# MCU.net
KiCad netlist of a schematic drawn in Altium Designer
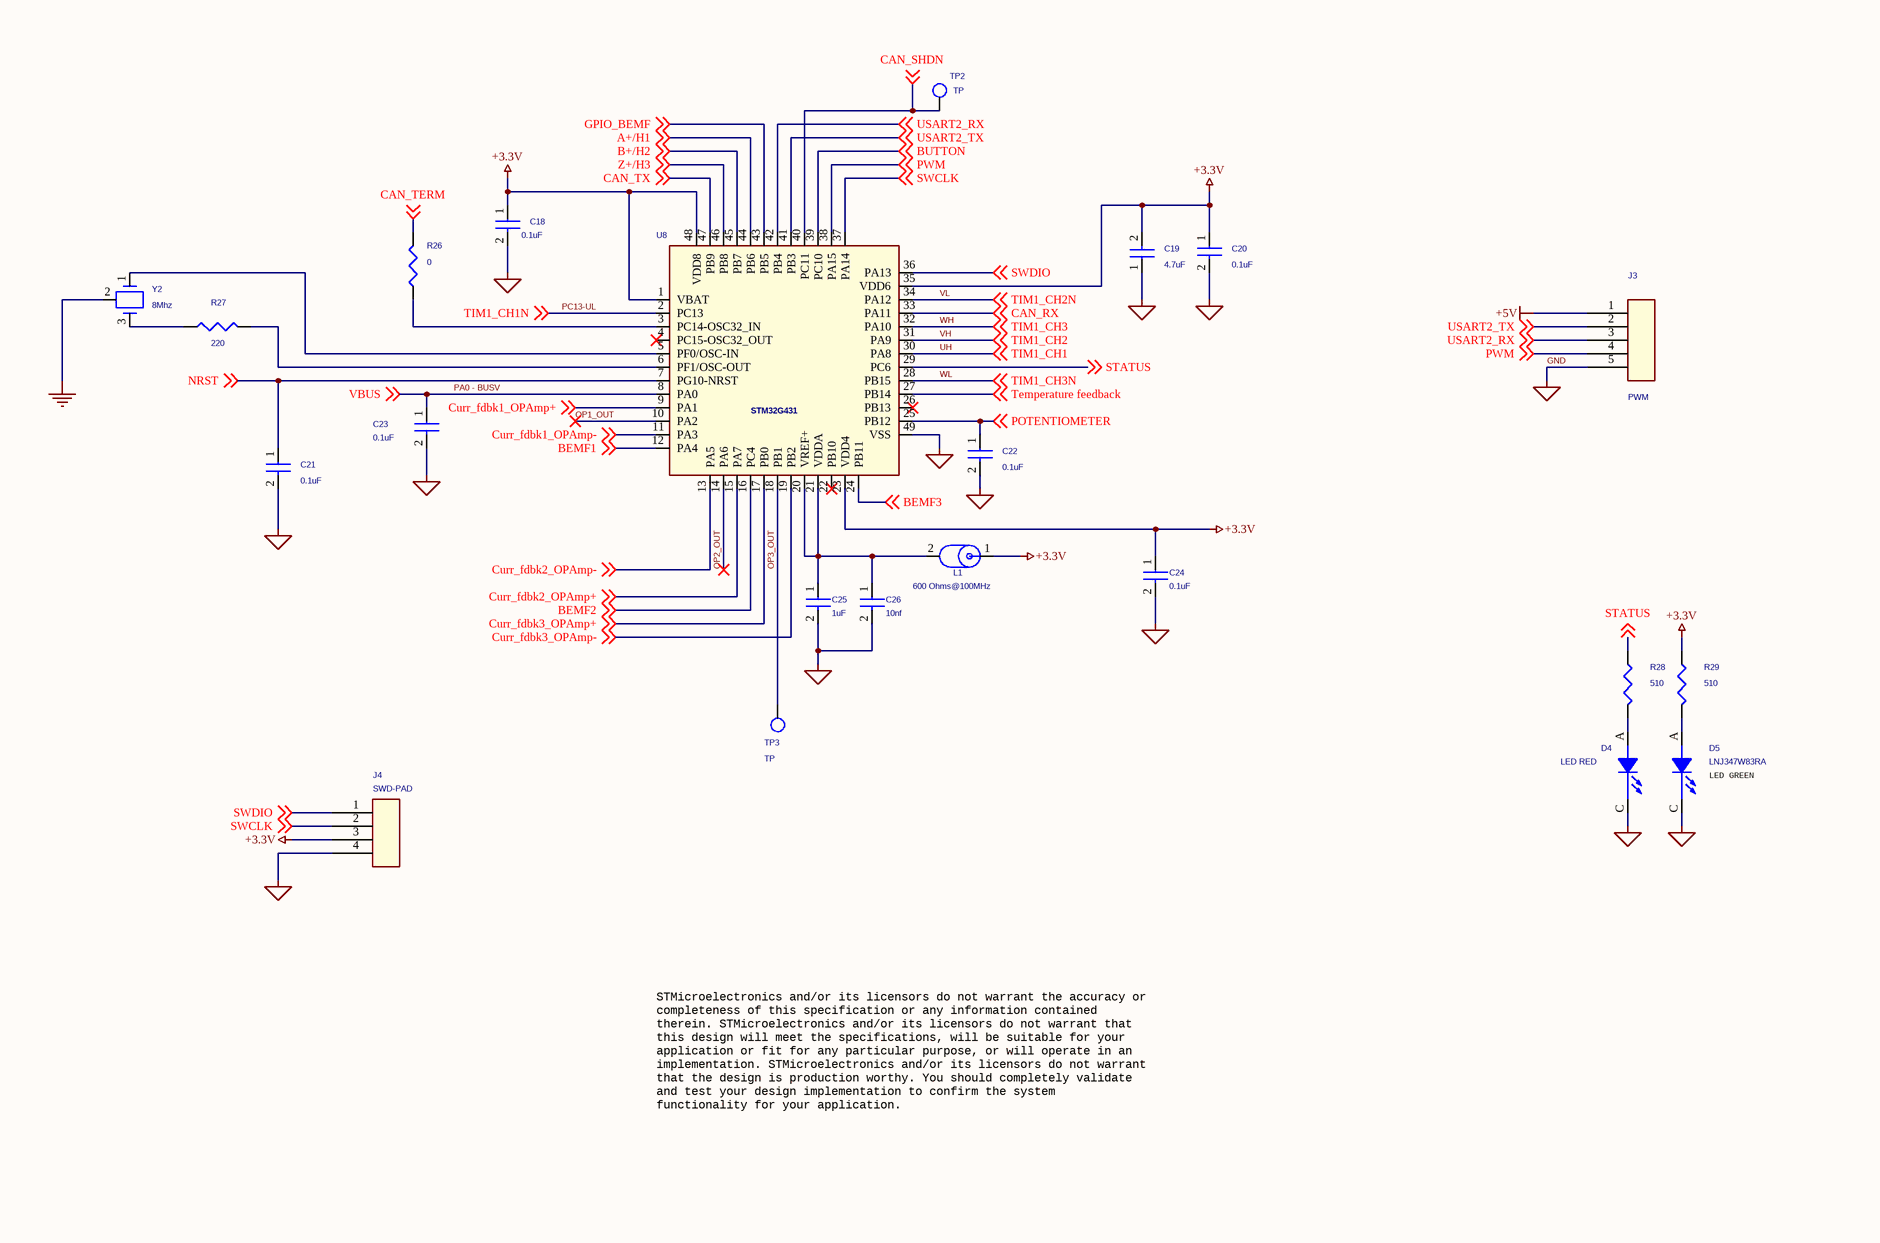
[diagram p0: MCU.SchDoc, top left]
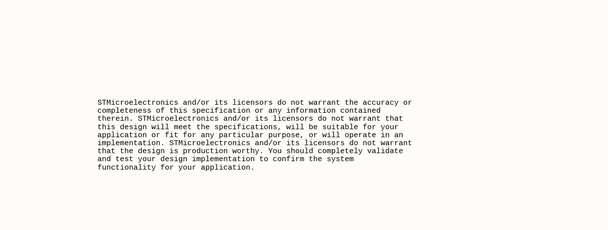
[diagram p1: MCU.SchDoc, bottom right]

(export (version "E")
  (design (tool "Eeschema 10.0.6"))
  (components
    (comp (ref "C18")
      (value "0.1uF")
      (footprint "C_0402")
      (description "CAP CER 0.1UF 16V X7R 0402")
      (fields (field (name "PART_NUMBER") "CAP-00000053") (field (name "TOLERANCE") "10%"))
      (libsource (lib "*") (part "CAP_Dup1"))
    )
    (comp (ref "C19")
      (value "4.7uF")
      (footprint "C_0603")
      (description "CAP CER 4.7UF 10V X5R 0603")
      (fields (field (name "MANUFACTURER") "Wurth Electronics Inc.") (field (name "TOLERANCE") "20%"))
      (libsource (lib "*") (part "CAP_Dup1"))
    )
    (comp (ref "C20")
      (value "0.1uF")
      (footprint "C_0402")
      (description "CAP CER 0.1UF 16V X7R 0402")
      (fields (field (name "MANUFACTURER") "Wurth Electronics Inc.") (field (name "TOLERANCE") "10%"))
      (libsource (lib "*") (part "CAP_Dup1"))
    )
    (comp (ref "C21")
      (value "0.1uF")
      (footprint "C_0402")
      (description "CAP CER 0.1UF 16V X7R 0402")
      (fields (field (name "MANUFACTURER") "Wurth Electronics Inc.") (field (name "TOLERANCE") "10%"))
      (libsource (lib "*") (part "CAP_Dup1"))
    )
    (comp (ref "C22")
      (value "0.1uF")
      (footprint "C_0402")
      (description "CAP CER 0.1UF 16V X7R 0402")
      (fields (field (name "PART_NUMBER") "CAP-00000053") (field (name "TOLERANCE") "10%"))
      (libsource (lib "*") (part "CAP_Dup1"))
    )
    (comp (ref "C23")
      (value "0.1uF")
      (footprint "C_0402")
      (description "CAP CER 0.1UF 16V X7R 0402")
      (fields (field (name "MANUFACTURER") "Wurth Electronics Inc.") (field (name "TOLERANCE") "10%"))
      (libsource (lib "*") (part "CAP_Dup1"))
    )
    (comp (ref "C24")
      (value "0.1uF")
      (footprint "C_0402")
      (description "CAP CER 0.1UF 16V X7R 0402")
      (fields (field (name "MANUFACTURER") "Wurth Electronics Inc.") (field (name "TOLERANCE") "10%"))
      (libsource (lib "*") (part "CAP_Dup1"))
    )
    (comp (ref "C25")
      (value "1uF")
      (footprint "C_0402")
      (description "CAP CER 1UF 25V X5R 0402")
      (fields (field (name "PART_NUMBER") "CAP-00000006") (field (name "TOLERANCE") "10%"))
      (libsource (lib "*") (part "CAP_Dup1"))
    )
    (comp (ref "C26")
      (value "10nf")
      (footprint "C_0402")
      (description "CAP CER 10000PF 16V X7R 0402")
      (fields (field (name "PART_NUMBER") "TMP-422") (field (name "TOLERANCE") "10%"))
      (libsource (lib "*") (part "CAP_Dup1"))
    )
    (comp (ref "D4")
      (value "LED RED")
      (footprint "D_0402_Led_red")
      (description "DIO, Rectangle with Flat Top, 1.00mm x 0.50mm, VLMS1500-GS08, 20mA, --, --, 0402 (1005 Metric)")
      (fields
        (field (name "PART_NUMBER") "DIO-00000003")
        (field (name "MANUFACTURER") "Vishay Semiconductor Opto Division")
      )
      (libsource (lib "*") (part "LED"))
    )
    (comp (ref "D5")
      (value "LNJ347W83RA")
      (footprint "D_0402_Led_green")
      (description "LED GREEN 0402 SMD")
      (fields
        (field (name "PART_NUMBER") "TMP-187")
        (field (name "MANUFACTURER") "Panasonic Electronic Components")
      )
      (libsource (lib "*") (part "LED"))
    )
    (comp (ref "J3")
      (value "PWM")
      (footprint "SOLDER_PAD_5PIN_SMD")
      (description "SOLDER PADS")
      (libsource (lib "*") (part "CON5"))
    )
    (comp (ref "J4")
      (value "SWD-PAD")
      (footprint "SOLDER_PAD_4PIN_rect_SMD")
      (description "SOLDER PADS")
      (libsource (lib "*") (part "CON4"))
    )
    (comp (ref "L1")
      (value "600 Ohms@100MHz")
      (footprint "L_0402")
      (description "FERRITE BEAD 600 OHM 0402 1LN")
      (fields
        (field (name "MANUFACTURER") "Murata Electronics North America")
        (field (name "PART_NUMBER") "TMP-492")
      )
      (libsource (lib "*") (part "IND_FB"))
    )
    (comp (ref "R26")
      (value "0")
      (footprint "R_0402")
      (description "RES SMD 0 OHM JUMPER 1/16W 0402")
      (fields (field (name "PART_NUMBER") "RES-00000073") (field (name "TOLERANCE") "Jumper"))
      (libsource (lib "*") (part "RES"))
    )
    (comp (ref "R27")
      (value "220")
      (footprint "R_0402")
      (description "RES SMD 220 OHM 1% 1/16W 0402")
      (fields (field (name "PART_NUMBER") "TMP-437") (field (name "TOLERANCE") "1%"))
      (libsource (lib "*") (part "RES"))
    )
    (comp (ref "R28")
      (value "510")
      (footprint "R_0402")
      (description "RES SMD 510 OHM 1% 1/16W 0402")
      (fields (field (name "PART_NUMBER") "TMP-438") (field (name "TOLERANCE") "1%"))
      (libsource (lib "*") (part "RES"))
    )
    (comp (ref "R29")
      (value "510")
      (footprint "R_0402")
      (description "RES SMD 510 OHM 1% 1/16W 0402")
      (fields (field (name "PART_NUMBER") "TMP-438") (field (name "TOLERANCE") "1%"))
      (libsource (lib "*") (part "RES"))
    )
    (comp (ref "TP2")
      (value "TP")
      (footprint "test_point_100_smd")
      (description "TEST POINT 1MM  SMD PADSTASCK")
      (fields (field (name "PART_NUMBER") "TMP-386"))
      (libsource (lib "*") (part "TESTPOINT"))
    )
    (comp (ref "TP3")
      (value "TP")
      (footprint "test_point_100_smd")
      (description "TEST POINT 1MM  SMD PADSTASCK")
      (fields (field (name "PART_NUMBER") "TMP-386"))
      (libsource (lib "*") (part "TESTPOINT"))
    )
    (comp (ref "U8")
      (value "STM32G431")
      (footprint "qfn49p50_700x700x60l40x25t560n")
      (libsource (lib "*") (part "STM32_LQFP64_6"))
    )
    (comp (ref "Y2")
      (value "8Mhz")
      (footprint "murata_cstce8m00g15c99-r0")
      (description "CER RES 8.0000MHZ 33PF SMD")
      (fields
        (field (name "MANUFACTURER") "Murata Electronics North America")
        (field (name "PART_NUMBER") "TMP-382")
      )
      (libsource (lib "*") (part "resonator"))
    )
  )
  (nets
    (net (code "1") (name "+3.3V") (class "Default")
      (node (ref "C18") (pin "1") (pinfunction "1_1") (pintype "passive"))
      (node (ref "C19") (pin "2") (pinfunction "2_2") (pintype "passive"))
      (node (ref "C20") (pin "1") (pinfunction "1_1") (pintype "passive"))
      (node (ref "C24") (pin "1") (pinfunction "1_1") (pintype "passive"))
      (node (ref "J4") (pin "3") (pinfunction "3_3") (pintype "passive"))
      (node (ref "L1") (pin "1") (pinfunction "1_1") (pintype "passive"))
      (node (ref "R29") (pin "1") (pinfunction "1_1") (pintype "passive"))
      (node (ref "U8") (pin "1") (pinfunction "VBAT_1") (pintype "passive"))
      (node (ref "U8") (pin "23") (pinfunction "VDD4_23") (pintype "passive"))
      (node (ref "U8") (pin "35") (pinfunction "VDD6_35") (pintype "passive"))
      (node (ref "U8") (pin "48") (pinfunction "VDD8_48") (pintype "passive"))
    )
    (net (code "2") (name "+5V") (class "Default")
      (node (ref "J3") (pin "1") (pinfunction "1_1") (pintype "passive"))
    )
    (net (code "3") (name "/OP1_OUT") (class "Default")
      (node (ref "U8") (pin "10") (pinfunction "PA2_10") (pintype "passive+no_connect"))
    )
    (net (code "4") (name "/OP2_OUT") (class "Default")
      (node (ref "U8") (pin "14") (pinfunction "PA6_14") (pintype "passive+no_connect"))
    )
    (net (code "5") (name "/OP3_OUT") (class "Default")
      (node (ref "TP3") (pin "1") (pinfunction "1_1") (pintype "passive"))
      (node (ref "U8") (pin "18") (pinfunction "PB1_18") (pintype "passive"))
    )
    (net (code "6") (name "A+{slash}H1") (class "Default")
      (node (ref "U8") (pin "44") (pinfunction "PB6_44") (pintype "passive"))
    )
    (net (code "7") (name "B+{slash}H2") (class "Default")
      (node (ref "U8") (pin "45") (pinfunction "PB7_45") (pintype "passive"))
    )
    (net (code "8") (name "BEMF1") (class "Default")
      (node (ref "U8") (pin "12") (pinfunction "PA4_12") (pintype "passive"))
    )
    (net (code "9") (name "BEMF2") (class "Default")
      (node (ref "U8") (pin "16") (pinfunction "PC4_16") (pintype "passive"))
    )
    (net (code "10") (name "BEMF3") (class "Default")
      (node (ref "U8") (pin "24") (pinfunction "PB11_24") (pintype "passive"))
    )
    (net (code "11") (name "BUTTON") (class "Default")
      (node (ref "U8") (pin "39") (pinfunction "PC10_39") (pintype "passive"))
    )
    (net (code "12") (name "CAN_RX") (class "Default")
      (node (ref "U8") (pin "33") (pinfunction "PA11_33") (pintype "passive"))
    )
    (net (code "13") (name "CAN_SHDN") (class "Default")
      (node (ref "TP2") (pin "1") (pinfunction "1_1") (pintype "passive"))
      (node (ref "U8") (pin "40") (pinfunction "PC11_40") (pintype "passive"))
    )
    (net (code "14") (name "CAN_TERM") (class "Default")
      (node (ref "R26") (pin "2") (pinfunction "2_2") (pintype "passive"))
    )
    (net (code "15") (name "CAN_TX") (class "Default")
      (node (ref "U8") (pin "47") (pinfunction "PB9_47") (pintype "passive"))
    )
    (net (code "16") (name "Curr_fdbk1_OPAmp+") (class "Default")
      (node (ref "U8") (pin "9") (pinfunction "PA1_9") (pintype "passive"))
    )
    (net (code "17") (name "Curr_fdbk1_OPAmp-") (class "Default")
      (node (ref "U8") (pin "11") (pinfunction "PA3_11") (pintype "passive"))
    )
    (net (code "18") (name "Curr_fdbk2_OPAmp+") (class "Default")
      (node (ref "U8") (pin "15") (pinfunction "PA7_15") (pintype "passive"))
    )
    (net (code "19") (name "Curr_fdbk2_OPAmp-") (class "Default")
      (node (ref "U8") (pin "13") (pinfunction "PA5_13") (pintype "passive"))
    )
    (net (code "20") (name "Curr_fdbk3_OPAmp+") (class "Default")
      (node (ref "U8") (pin "17") (pinfunction "PB0_17") (pintype "passive"))
    )
    (net (code "21") (name "Curr_fdbk3_OPAmp-") (class "Default")
      (node (ref "U8") (pin "19") (pinfunction "PB2_19") (pintype "passive"))
    )
    (net (code "22") (name "GND") (class "Default")
      (node (ref "C18") (pin "2") (pinfunction "2_2") (pintype "passive"))
      (node (ref "C19") (pin "1") (pinfunction "1_1") (pintype "passive"))
      (node (ref "C20") (pin "2") (pinfunction "2_2") (pintype "passive"))
      (node (ref "C21") (pin "2") (pinfunction "2_2") (pintype "passive"))
      (node (ref "C22") (pin "2") (pinfunction "2_2") (pintype "passive"))
      (node (ref "C23") (pin "2") (pinfunction "2_2") (pintype "passive"))
      (node (ref "C24") (pin "2") (pinfunction "2_2") (pintype "passive"))
      (node (ref "C25") (pin "2") (pinfunction "2_2") (pintype "passive"))
      (node (ref "C26") (pin "2") (pinfunction "2_2") (pintype "passive"))
      (node (ref "D4") (pin "C") (pinfunction "CATHODE_C") (pintype "passive"))
      (node (ref "D5") (pin "C") (pinfunction "CATHODE_C") (pintype "passive"))
      (node (ref "J3") (pin "5") (pinfunction "5_5") (pintype "passive"))
      (node (ref "J4") (pin "4") (pinfunction "4_4") (pintype "passive"))
      (node (ref "U8") (pin "49") (pinfunction "VSS_49") (pintype "passive"))
      (node (ref "Y2") (pin "2") (pinfunction "2_2") (pintype "passive"))
    )
    (net (code "23") (name "GPIO_BEMF") (class "Default")
      (node (ref "U8") (pin "43") (pinfunction "PB5_43") (pintype "passive"))
    )
    (net (code "24") (name "NRST") (class "Default")
      (node (ref "C21") (pin "1") (pinfunction "1_1") (pintype "passive"))
      (node (ref "U8") (pin "7") (pinfunction "PG10-NRST_7") (pintype "passive"))
    )
    (net (code "25") (name "Net-(D4-ANODE)") (class "Default")
      (node (ref "D4") (pin "A") (pinfunction "ANODE_A") (pintype "passive"))
      (node (ref "R28") (pin "2") (pinfunction "2_2") (pintype "passive"))
    )
    (net (code "26") (name "Net-(D5-ANODE)") (class "Default")
      (node (ref "D5") (pin "A") (pinfunction "ANODE_A") (pintype "passive"))
      (node (ref "R29") (pin "2") (pinfunction "2_2") (pintype "passive"))
    )
    (net (code "27") (name "Net-(R27-Pad1)") (class "Default")
      (node (ref "R27") (pin "1") (pinfunction "1_1") (pintype "passive"))
      (node (ref "Y2") (pin "3") (pinfunction "3_3") (pintype "passive"))
    )
    (net (code "28") (name "Net-(U8-PC14-OSC32_IN)") (class "Default")
      (node (ref "R26") (pin "1") (pinfunction "1_1") (pintype "passive"))
      (node (ref "U8") (pin "3") (pinfunction "PC14-OSC32_IN_3") (pintype "passive"))
    )
    (net (code "29") (name "Net-(U8-PF0{slash}OSC-IN)") (class "Default")
      (node (ref "U8") (pin "5") (pinfunction "PF0/OSC-IN_5") (pintype "passive"))
      (node (ref "Y2") (pin "1") (pinfunction "1_1") (pintype "passive"))
    )
    (net (code "30") (name "Net-(U8-PF1{slash}OSC-OUT)") (class "Default")
      (node (ref "R27") (pin "2") (pinfunction "2_2") (pintype "passive"))
      (node (ref "U8") (pin "6") (pinfunction "PF1/OSC-OUT_6") (pintype "passive"))
    )
    (net (code "31") (name "Net-(U8-VDDA)") (class "Default")
      (node (ref "C25") (pin "1") (pinfunction "1_1") (pintype "passive"))
      (node (ref "C26") (pin "1") (pinfunction "1_1") (pintype "passive"))
      (node (ref "L1") (pin "2") (pinfunction "2_2") (pintype "passive"))
      (node (ref "U8") (pin "20") (pinfunction "VREF+_20") (pintype "passive"))
      (node (ref "U8") (pin "21") (pinfunction "VDDA_21") (pintype "passive"))
    )
    (net (code "32") (name "POTENTIOMETER") (class "Default")
      (node (ref "C22") (pin "1") (pinfunction "1_1") (pintype "passive"))
      (node (ref "U8") (pin "25") (pinfunction "PB12_25") (pintype "passive"))
    )
    (net (code "33") (name "PWM") (class "Default")
      (node (ref "J3") (pin "4") (pinfunction "4_4") (pintype "passive"))
      (node (ref "U8") (pin "38") (pinfunction "PA15_38") (pintype "passive"))
    )
    (net (code "34") (name "STATUS") (class "Default")
      (node (ref "R28") (pin "1") (pinfunction "1_1") (pintype "passive"))
      (node (ref "U8") (pin "29") (pinfunction "PC6_29") (pintype "passive"))
    )
    (net (code "35") (name "SWCLK") (class "Default")
      (node (ref "J4") (pin "2") (pinfunction "2_2") (pintype "passive"))
      (node (ref "U8") (pin "37") (pinfunction "PA14_37") (pintype "passive"))
    )
    (net (code "36") (name "SWDIO") (class "Default")
      (node (ref "J4") (pin "1") (pinfunction "1_1") (pintype "passive"))
      (node (ref "U8") (pin "36") (pinfunction "PA13_36") (pintype "passive"))
    )
    (net (code "37") (name "TIM1_CH1") (class "Default")
      (node (ref "U8") (pin "30") (pinfunction "PA8_30") (pintype "passive"))
    )
    (net (code "38") (name "TIM1_CH1N") (class "Default")
      (node (ref "U8") (pin "2") (pinfunction "PC13_2") (pintype "passive"))
    )
    (net (code "39") (name "TIM1_CH2") (class "Default")
      (node (ref "U8") (pin "31") (pinfunction "PA9_31") (pintype "passive"))
    )
    (net (code "40") (name "TIM1_CH2N") (class "Default")
      (node (ref "U8") (pin "34") (pinfunction "PA12_34") (pintype "passive"))
    )
    (net (code "41") (name "TIM1_CH3") (class "Default")
      (node (ref "U8") (pin "32") (pinfunction "PA10_32") (pintype "passive"))
    )
    (net (code "42") (name "TIM1_CH3N") (class "Default")
      (node (ref "U8") (pin "28") (pinfunction "PB15_28") (pintype "passive"))
    )
    (net (code "43") (name "Temperature feedback") (class "Default")
      (node (ref "U8") (pin "27") (pinfunction "PB14_27") (pintype "passive"))
    )
    (net (code "44") (name "USART2_RX") (class "Default")
      (node (ref "J3") (pin "3") (pinfunction "3_3") (pintype "passive"))
      (node (ref "U8") (pin "42") (pinfunction "PB4_42") (pintype "passive"))
    )
    (net (code "45") (name "USART2_TX") (class "Default")
      (node (ref "J3") (pin "2") (pinfunction "2_2") (pintype "passive"))
      (node (ref "U8") (pin "41") (pinfunction "PB3_41") (pintype "passive"))
    )
    (net (code "46") (name "VBUS") (class "Default")
      (node (ref "C23") (pin "1") (pinfunction "1_1") (pintype "passive"))
      (node (ref "U8") (pin "8") (pinfunction "PA0_8") (pintype "passive"))
    )
    (net (code "47") (name "Z+{slash}H3") (class "Default")
      (node (ref "U8") (pin "46") (pinfunction "PB8_46") (pintype "passive"))
    )
    (net (code "48") (name "unconnected-(U8-PB10-Pad22)") (class "Default")
      (node (ref "U8") (pin "22") (pinfunction "PB10_22") (pintype "passive+no_connect"))
    )
    (net (code "49") (name "unconnected-(U8-PB13-Pad26)") (class "Default")
      (node (ref "U8") (pin "26") (pinfunction "PB13_26") (pintype "passive+no_connect"))
    )
    (net (code "50") (name "unconnected-(U8-PC15-OSC32_OUT-Pad4)") (class "Default")
      (node (ref "U8") (pin "4") (pinfunction "PC15-OSC32_OUT_4") (pintype "passive+no_connect"))
    )
  )
)
